# Schematic_withShiftResister.net
KiCad netlist of a schematic drawn in EAGLE
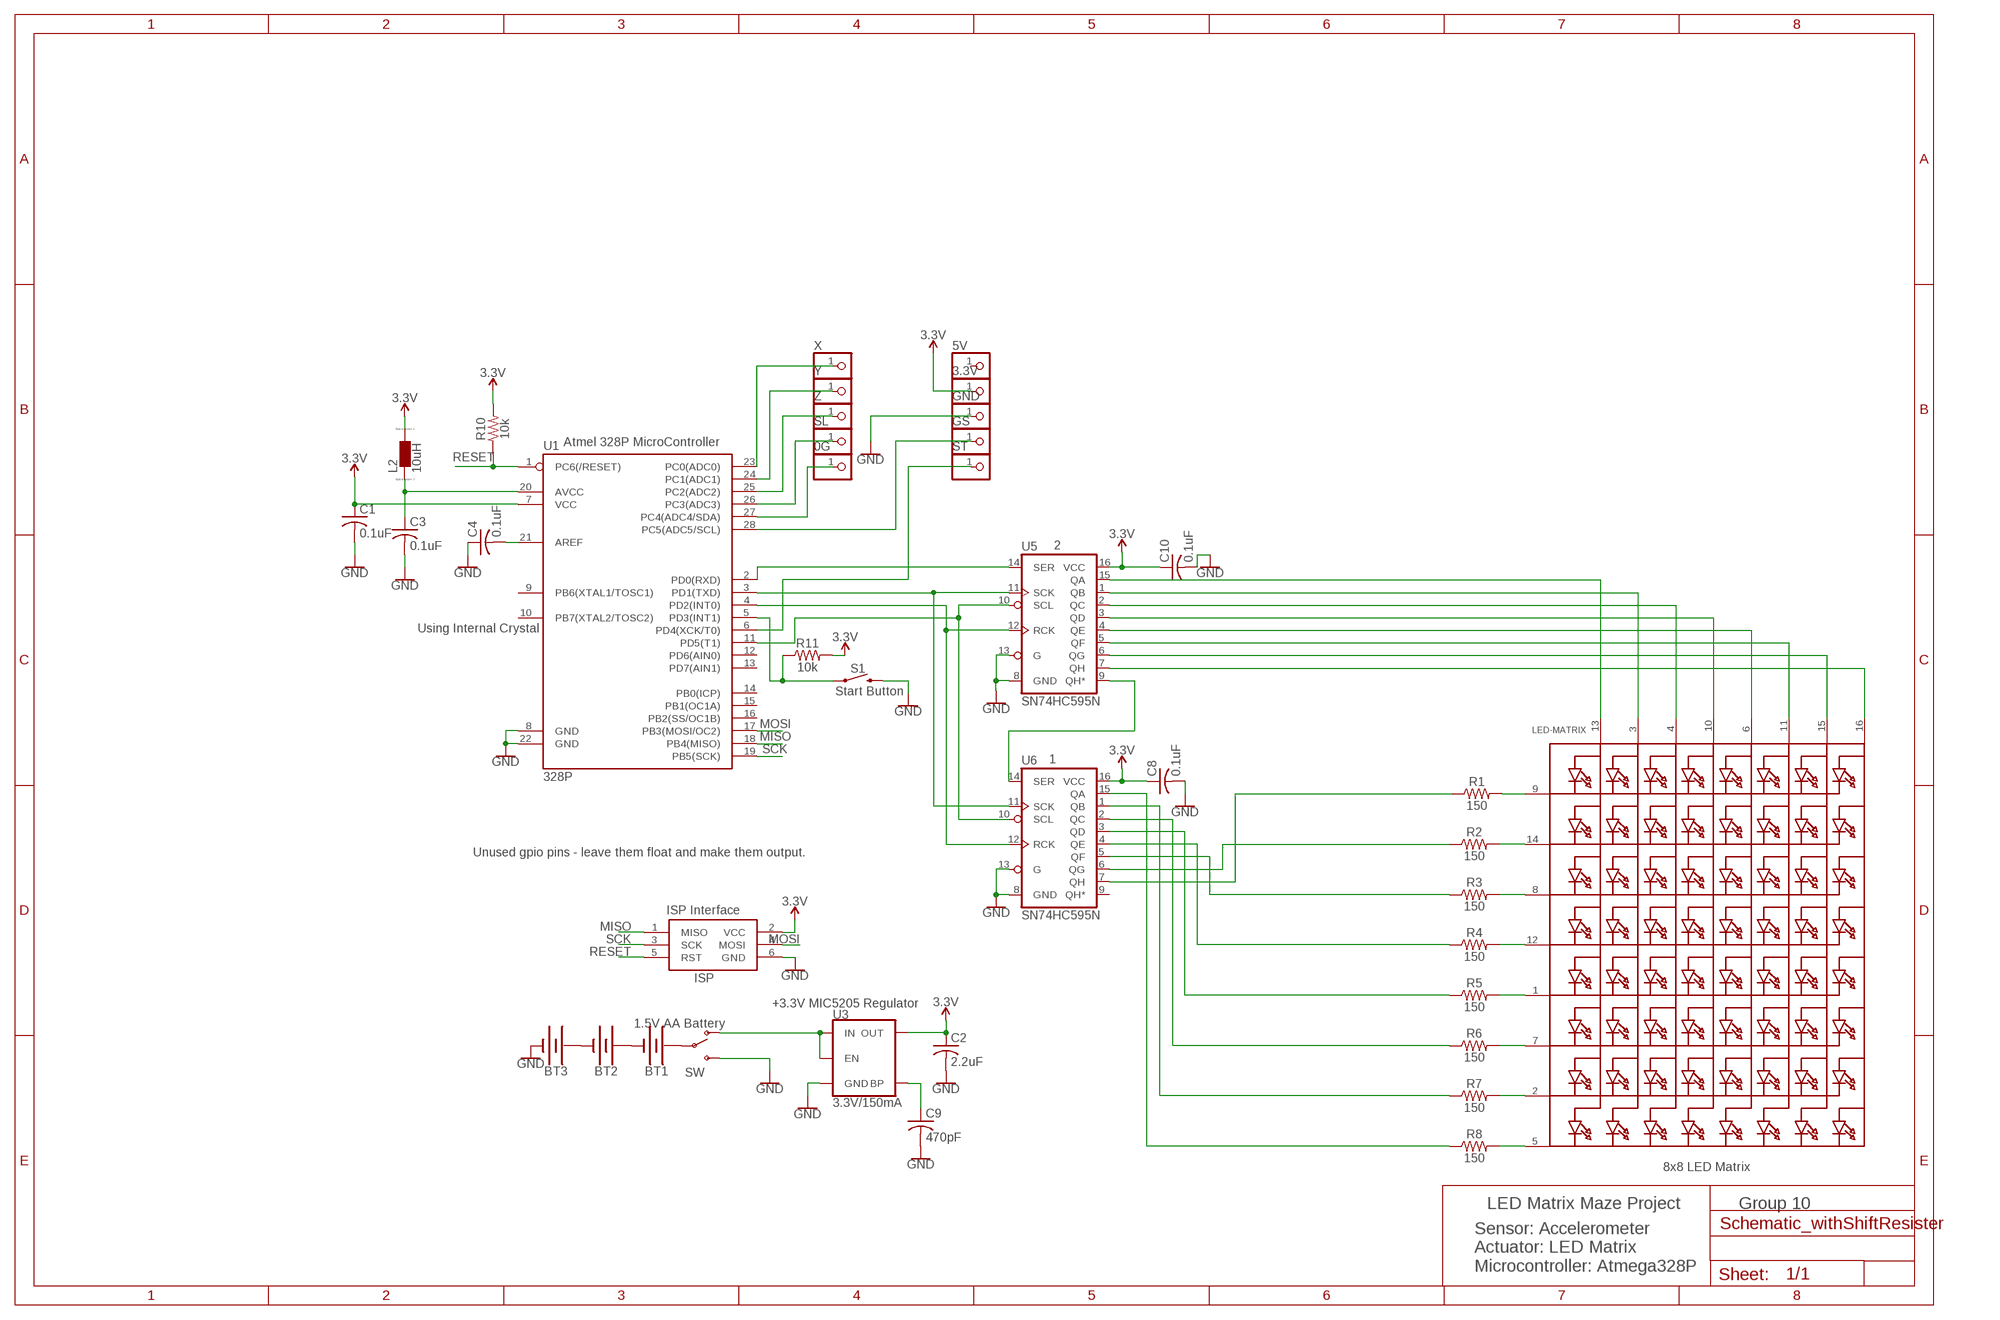
[diagram p0: schematic, sheet 1]

(export (version "E")
  (design (tool "Eeschema 10.0.6"))
  (components
    (comp (ref "0G")
      (value "PINHD-1X1")
      (footprint "eagle-import:1X01")
      (libsource (lib "eagle-import") (part "PINHD-1X1"))
    )
    (comp (ref "3.3V")
      (value "PINHD-1X1")
      (footprint "eagle-import:1X01")
      (libsource (lib "eagle-import") (part "PINHD-1X1"))
    )
    (comp (ref "5V")
      (value "PINHD-1X1")
      (footprint "eagle-import:1X01")
      (libsource (lib "eagle-import") (part "PINHD-1X1"))
    )
    (comp (ref "BT1")
      (value "BATTERY-AAA_KIT")
      (footprint "eagle-import:BATTERY-AAA-KIT")
      (libsource (lib "eagle-import") (part "BATTERY-AAA_KIT"))
    )
    (comp (ref "BT2")
      (value "BATTERY-AAA_KIT")
      (footprint "eagle-import:BATTERY-AAA-KIT")
      (libsource (lib "eagle-import") (part "BATTERY-AAA_KIT"))
    )
    (comp (ref "BT3")
      (value "BATTERY-AAA_KIT")
      (footprint "eagle-import:BATTERY-AAA-KIT")
      (libsource (lib "eagle-import") (part "BATTERY-AAA_KIT"))
    )
    (comp (ref "C1")
      (value "0.1uF")
      (footprint "eagle-import:C0805")
      (libsource (lib "eagle-import") (part "C-USC0805"))
    )
    (comp (ref "C2")
      (value "2.2uF")
      (footprint "eagle-import:C0805")
      (libsource (lib "eagle-import") (part "C-USC0805"))
    )
    (comp (ref "C3")
      (value "0.1uF")
      (footprint "eagle-import:C0805")
      (libsource (lib "eagle-import") (part "C-USC0805"))
    )
    (comp (ref "C4")
      (value "0.1uF")
      (footprint "eagle-import:C0805")
      (libsource (lib "eagle-import") (part "C-USC0805"))
    )
    (comp (ref "C8")
      (value "0.1uF")
      (footprint "eagle-import:C0805")
      (libsource (lib "eagle-import") (part "C-USC0805"))
    )
    (comp (ref "C9")
      (value "470pF")
      (footprint "eagle-import:C0805")
      (libsource (lib "eagle-import") (part "C-USC0805"))
    )
    (comp (ref "C10")
      (value "0.1uF")
      (footprint "eagle-import:C0805")
      (libsource (lib "eagle-import") (part "C-USC0805"))
    )
    (comp (ref "GND")
      (value "PINHD-1X1")
      (footprint "eagle-import:1X01")
      (libsource (lib "eagle-import") (part "PINHD-1X1"))
    )
    (comp (ref "GS")
      (value "PINHD-1X1")
      (footprint "eagle-import:1X01")
      (libsource (lib "eagle-import") (part "PINHD-1X1"))
    )
    (comp (ref "ISP")
      (value "AVRISP-6")
      (footprint "eagle-import:AVRISP")
      (libsource (lib "eagle-import") (part "AVRISP-6"))
    )
    (comp (ref "L2")
      (value "10uH")
      (footprint "eagle-import:L1812")
      (libsource (lib "eagle-import") (part "L"))
    )
    (comp (ref "LED-MATRIX")
      (value "SEGMENT_8X8_ROWCATHODEM12A881UR")
      (footprint "eagle-import:SEGMENT_BL-M12A881UR")
      (libsource (lib "eagle-import") (part "SEGMENT_8X8_ROWCATHODEM12A881UR"))
    )
    (comp (ref "R1")
      (value "150")
      (footprint "eagle-import:0603")
      (libsource (lib "eagle-import") (part "150OHM-0603-1/10W-1%"))
    )
    (comp (ref "R2")
      (value "150")
      (footprint "eagle-import:0603")
      (libsource (lib "eagle-import") (part "150OHM-0603-1/10W-1%"))
    )
    (comp (ref "R3")
      (value "150")
      (footprint "eagle-import:0603")
      (libsource (lib "eagle-import") (part "150OHM-0603-1/10W-1%"))
    )
    (comp (ref "R4")
      (value "150")
      (footprint "eagle-import:0603")
      (libsource (lib "eagle-import") (part "150OHM-0603-1/10W-1%"))
    )
    (comp (ref "R5")
      (value "150")
      (footprint "eagle-import:0603")
      (libsource (lib "eagle-import") (part "150OHM-0603-1/10W-1%"))
    )
    (comp (ref "R6")
      (value "150")
      (footprint "eagle-import:0603")
      (libsource (lib "eagle-import") (part "150OHM-0603-1/10W-1%"))
    )
    (comp (ref "R7")
      (value "150")
      (footprint "eagle-import:0603")
      (libsource (lib "eagle-import") (part "150OHM-0603-1/10W-1%"))
    )
    (comp (ref "R8")
      (value "150")
      (footprint "eagle-import:0603")
      (libsource (lib "eagle-import") (part "150OHM-0603-1/10W-1%"))
    )
    (comp (ref "R10")
      (value "10k")
      (footprint "eagle-import:0603")
      (libsource (lib "eagle-import") (part "10KOHM-0603-1/10W-1%"))
    )
    (comp (ref "R11")
      (value "10k")
      (footprint "eagle-import:0603")
      (libsource (lib "eagle-import") (part "10KOHM-0603-1/10W-1%"))
    )
    (comp (ref "S1")
      (value "MOMENTARY-SWITCH-SPST-PTH-6.0MM")
      (footprint "eagle-import:TACTILE_SWITCH_PTH_6.0MM")
      (libsource (lib "eagle-import") (part "MOMENTARY-SWITCH-SPST-PTH-6.0MM"))
    )
    (comp (ref "SL")
      (value "PINHD-1X1")
      (footprint "eagle-import:1X01")
      (libsource (lib "eagle-import") (part "PINHD-1X1"))
    )
    (comp (ref "ST")
      (value "PINHD-1X1")
      (footprint "eagle-import:1X01")
      (libsource (lib "eagle-import") (part "PINHD-1X1"))
    )
    (comp (ref "SW")
      (value "SWITCH-SPSTPTH_LOCK")
      (footprint "eagle-import:SWITCH-SPDT_LOCK.007S")
      (libsource (lib "eagle-import") (part "SWITCH-SPSTPTH_LOCK"))
    )
    (comp (ref "U1")
      (value "328P")
      (footprint "eagle-import:DIP28")
      (libsource (lib "eagle-import") (part "ATMEGA328P_PDIP"))
    )
    (comp (ref "U3")
      (value "3.3V/150mA")
      (footprint "eagle-import:SOT23-5")
      (libsource (lib "eagle-import") (part "V_REG_MIC52053.3V"))
    )
    (comp (ref "U5")
      (value "SN74HC595N")
      (footprint "eagle-import:DIP16")
      (libsource (lib "eagle-import") (part "74595NHC"))
    )
    (comp (ref "U6")
      (value "SN74HC595N")
      (footprint "eagle-import:DIP16")
      (libsource (lib "eagle-import") (part "74595NHC"))
    )
    (comp (ref "X")
      (value "PINHD-1X1")
      (footprint "eagle-import:1X01")
      (libsource (lib "eagle-import") (part "PINHD-1X1"))
    )
    (comp (ref "Y")
      (value "PINHD-1X1")
      (footprint "eagle-import:1X01")
      (libsource (lib "eagle-import") (part "PINHD-1X1"))
    )
    (comp (ref "Z")
      (value "PINHD-1X1")
      (footprint "eagle-import:1X01")
      (libsource (lib "eagle-import") (part "PINHD-1X1"))
    )
  )
  (nets
    (net (code "1") (name "/MISO") (class "Default")
      (node (ref "ISP") (pin "1") (pinfunction "MISO_1") (pintype "input"))
      (node (ref "U1") (pin "18") (pinfunction "PB4(MISO)_18") (pintype "bidirectional"))
    )
    (net (code "2") (name "/MOSI") (class "Default")
      (node (ref "ISP") (pin "4") (pinfunction "MOSI_4") (pintype "output"))
      (node (ref "U1") (pin "17") (pinfunction "PB3(MOSI/OC2)_17") (pintype "bidirectional"))
    )
    (net (code "3") (name "/RESET") (class "Default")
      (node (ref "ISP") (pin "5") (pinfunction "RST_5") (pintype "output"))
      (node (ref "R10") (pin "1") (pinfunction "1_1") (pintype "passive"))
      (node (ref "U1") (pin "1") (pinfunction "PC6(/RESET)_1") (pintype "bidirectional"))
    )
    (net (code "4") (name "/SCK") (class "Default")
      (node (ref "ISP") (pin "3") (pinfunction "SCK_3") (pintype "output"))
      (node (ref "U1") (pin "19") (pinfunction "PB5(SCK)_19") (pintype "bidirectional"))
    )
    (net (code "5") (name "3.3V") (class "Default")
      (node (ref "3.3V") (pin "1") (pinfunction "1_1") (pintype "passive"))
      (node (ref "C1") (pin "1") (pinfunction "1_1") (pintype "passive"))
      (node (ref "C10") (pin "1") (pinfunction "1_1") (pintype "passive"))
      (node (ref "C2") (pin "1") (pinfunction "1_1") (pintype "passive"))
      (node (ref "C8") (pin "1") (pinfunction "1_1") (pintype "passive"))
      (node (ref "ISP") (pin "2") (pinfunction "VCC_2") (pintype "power_in"))
      (node (ref "L2") (pin "1") (pinfunction "1_1") (pintype "passive"))
      (node (ref "R10") (pin "2") (pinfunction "2_2") (pintype "passive"))
      (node (ref "R11") (pin "2") (pinfunction "2_2") (pintype "passive"))
      (node (ref "U1") (pin "7") (pinfunction "VCC_7") (pintype "bidirectional"))
      (node (ref "U3") (pin "5") (pinfunction "OUT_5") (pintype "passive"))
      (node (ref "U5") (pin "16") (pinfunction "VCC_16") (pintype "power_in"))
      (node (ref "U6") (pin "16") (pinfunction "VCC_16") (pintype "power_in"))
    )
    (net (code "6") (name "GND") (class "Default")
      (node (ref "BT3") (pin "GND@1") (pinfunction "-_GND@1") (pintype "power_in"))
      (node (ref "C1") (pin "2") (pinfunction "2_2") (pintype "passive"))
      (node (ref "C10") (pin "2") (pinfunction "2_2") (pintype "passive"))
      (node (ref "C2") (pin "2") (pinfunction "2_2") (pintype "passive"))
      (node (ref "C3") (pin "2") (pinfunction "2_2") (pintype "passive"))
      (node (ref "C4") (pin "1") (pinfunction "1_1") (pintype "passive"))
      (node (ref "C8") (pin "2") (pinfunction "2_2") (pintype "passive"))
      (node (ref "C9") (pin "2") (pinfunction "2_2") (pintype "passive"))
      (node (ref "GND") (pin "1") (pinfunction "1_1") (pintype "passive"))
      (node (ref "ISP") (pin "6") (pinfunction "GND_6") (pintype "power_in"))
      (node (ref "S1") (pin "3") (pinfunction "2_3") (pintype "passive"))
      (node (ref "SW") (pin "3") (pinfunction "S_3") (pintype "passive"))
      (node (ref "U1") (pin "22") (pinfunction "GND_22") (pintype "bidirectional"))
      (node (ref "U1") (pin "8") (pinfunction "GND_8") (pintype "bidirectional"))
      (node (ref "U3") (pin "2") (pinfunction "GND_2") (pintype "input"))
      (node (ref "U5") (pin "13") (pinfunction "G_13") (pintype "input"))
      (node (ref "U5") (pin "8") (pinfunction "GND_8") (pintype "power_in"))
      (node (ref "U6") (pin "13") (pinfunction "G_13") (pintype "input"))
      (node (ref "U6") (pin "8") (pinfunction "GND_8") (pintype "power_in"))
    )
    (net (code "7") (name "Net-(BT1-+)") (class "Default")
      (node (ref "BT1") (pin "PWR@1") (pinfunction "+_PWR@1") (pintype "power_in"))
      (node (ref "SW") (pin "2") (pinfunction "P_2") (pintype "passive"))
    )
    (net (code "8") (name "Net-(BT1--)") (class "Default")
      (node (ref "BT1") (pin "GND@1") (pinfunction "-_GND@1") (pintype "power_in"))
      (node (ref "BT2") (pin "PWR@1") (pinfunction "+_PWR@1") (pintype "power_in"))
    )
    (net (code "9") (name "Net-(BT2--)") (class "Default")
      (node (ref "BT2") (pin "GND@1") (pinfunction "-_GND@1") (pintype "power_in"))
      (node (ref "BT3") (pin "PWR@1") (pinfunction "+_PWR@1") (pintype "power_in"))
    )
    (net (code "10") (name "Net-(LED-MATRIX-A1)") (class "Default")
      (node (ref "LED-MATRIX") (pin "13") (pinfunction "A1_13") (pintype "bidirectional"))
      (node (ref "U5") (pin "15") (pinfunction "QA_15") (pintype "tri_state"))
    )
    (net (code "11") (name "Net-(LED-MATRIX-A2)") (class "Default")
      (node (ref "LED-MATRIX") (pin "3") (pinfunction "A2_3") (pintype "bidirectional"))
      (node (ref "U5") (pin "1") (pinfunction "QB_1") (pintype "tri_state"))
    )
    (net (code "12") (name "Net-(LED-MATRIX-A3)") (class "Default")
      (node (ref "LED-MATRIX") (pin "4") (pinfunction "A3_4") (pintype "bidirectional"))
      (node (ref "U5") (pin "2") (pinfunction "QC_2") (pintype "tri_state"))
    )
    (net (code "13") (name "Net-(LED-MATRIX-A4)") (class "Default")
      (node (ref "LED-MATRIX") (pin "10") (pinfunction "A4_10") (pintype "bidirectional"))
      (node (ref "U5") (pin "3") (pinfunction "QD_3") (pintype "tri_state"))
    )
    (net (code "14") (name "Net-(LED-MATRIX-A5)") (class "Default")
      (node (ref "LED-MATRIX") (pin "6") (pinfunction "A5_6") (pintype "bidirectional"))
      (node (ref "U5") (pin "4") (pinfunction "QE_4") (pintype "tri_state"))
    )
    (net (code "15") (name "Net-(LED-MATRIX-A6)") (class "Default")
      (node (ref "LED-MATRIX") (pin "11") (pinfunction "A6_11") (pintype "bidirectional"))
      (node (ref "U5") (pin "5") (pinfunction "QF_5") (pintype "tri_state"))
    )
    (net (code "16") (name "Net-(LED-MATRIX-A7)") (class "Default")
      (node (ref "LED-MATRIX") (pin "15") (pinfunction "A7_15") (pintype "bidirectional"))
      (node (ref "U5") (pin "6") (pinfunction "QG_6") (pintype "tri_state"))
    )
    (net (code "17") (name "Net-(LED-MATRIX-A8)") (class "Default")
      (node (ref "LED-MATRIX") (pin "16") (pinfunction "A8_16") (pintype "bidirectional"))
      (node (ref "U5") (pin "7") (pinfunction "QH_7") (pintype "tri_state"))
    )
    (net (code "18") (name "Net-(LED-MATRIX-K1)") (class "Default")
      (node (ref "LED-MATRIX") (pin "9") (pinfunction "K1_9") (pintype "bidirectional"))
      (node (ref "R1") (pin "2") (pinfunction "2_2") (pintype "passive"))
    )
    (net (code "19") (name "Net-(LED-MATRIX-K2)") (class "Default")
      (node (ref "LED-MATRIX") (pin "14") (pinfunction "K2_14") (pintype "bidirectional"))
      (node (ref "R2") (pin "2") (pinfunction "2_2") (pintype "passive"))
    )
    (net (code "20") (name "Net-(LED-MATRIX-K3)") (class "Default")
      (node (ref "LED-MATRIX") (pin "8") (pinfunction "K3_8") (pintype "bidirectional"))
      (node (ref "R3") (pin "2") (pinfunction "2_2") (pintype "passive"))
    )
    (net (code "21") (name "Net-(LED-MATRIX-K4)") (class "Default")
      (node (ref "LED-MATRIX") (pin "12") (pinfunction "K4_12") (pintype "bidirectional"))
      (node (ref "R4") (pin "2") (pinfunction "2_2") (pintype "passive"))
    )
    (net (code "22") (name "Net-(LED-MATRIX-K5)") (class "Default")
      (node (ref "LED-MATRIX") (pin "1") (pinfunction "K5_1") (pintype "bidirectional"))
      (node (ref "R5") (pin "2") (pinfunction "2_2") (pintype "passive"))
    )
    (net (code "23") (name "Net-(LED-MATRIX-K6)") (class "Default")
      (node (ref "LED-MATRIX") (pin "7") (pinfunction "K6_7") (pintype "bidirectional"))
      (node (ref "R6") (pin "2") (pinfunction "2_2") (pintype "passive"))
    )
    (net (code "24") (name "Net-(LED-MATRIX-K7)") (class "Default")
      (node (ref "LED-MATRIX") (pin "2") (pinfunction "K7_2") (pintype "bidirectional"))
      (node (ref "R7") (pin "2") (pinfunction "2_2") (pintype "passive"))
    )
    (net (code "25") (name "Net-(LED-MATRIX-K8)") (class "Default")
      (node (ref "LED-MATRIX") (pin "5") (pinfunction "K8_5") (pintype "bidirectional"))
      (node (ref "R8") (pin "2") (pinfunction "2_2") (pintype "passive"))
    )
    (net (code "26") (name "Net-(SW-O)") (class "Default")
      (node (ref "SW") (pin "1") (pinfunction "O_1") (pintype "passive"))
      (node (ref "U3") (pin "1") (pinfunction "IN_1") (pintype "input"))
      (node (ref "U3") (pin "3") (pinfunction "EN_3") (pintype "input"))
    )
    (net (code "27") (name "Net-(U1-AREF)") (class "Default")
      (node (ref "C4") (pin "2") (pinfunction "2_2") (pintype "passive"))
      (node (ref "U1") (pin "21") (pinfunction "AREF_21") (pintype "bidirectional"))
    )
    (net (code "28") (name "Net-(U1-AVCC)") (class "Default")
      (node (ref "C3") (pin "1") (pinfunction "1_1") (pintype "passive"))
      (node (ref "L2") (pin "2") (pinfunction "2_2") (pintype "passive"))
      (node (ref "U1") (pin "20") (pinfunction "AVCC_20") (pintype "bidirectional"))
    )
    (net (code "29") (name "Net-(U1-PC0(ADC0))") (class "Default")
      (node (ref "U1") (pin "23") (pinfunction "PC0(ADC0)_23") (pintype "bidirectional"))
      (node (ref "X") (pin "1") (pinfunction "1_1") (pintype "passive"))
    )
    (net (code "30") (name "Net-(U1-PC1(ADC1))") (class "Default")
      (node (ref "U1") (pin "24") (pinfunction "PC1(ADC1)_24") (pintype "bidirectional"))
      (node (ref "Y") (pin "1") (pinfunction "1_1") (pintype "passive"))
    )
    (net (code "31") (name "Net-(U1-PC2(ADC2))") (class "Default")
      (node (ref "U1") (pin "25") (pinfunction "PC2(ADC2)_25") (pintype "bidirectional"))
      (node (ref "Z") (pin "1") (pinfunction "1_1") (pintype "passive"))
    )
    (net (code "32") (name "Net-(U1-PC3(ADC3))") (class "Default")
      (node (ref "SL") (pin "1") (pinfunction "1_1") (pintype "passive"))
      (node (ref "U1") (pin "26") (pinfunction "PC3(ADC3)_26") (pintype "bidirectional"))
    )
    (net (code "33") (name "Net-(U1-PC4(ADC4{slash}SDA))") (class "Default")
      (node (ref "0G") (pin "1") (pinfunction "1_1") (pintype "passive"))
      (node (ref "U1") (pin "27") (pinfunction "PC4(ADC4/SDA)_27") (pintype "bidirectional"))
    )
    (net (code "34") (name "Net-(U1-PC5(ADC5{slash}SCL))") (class "Default")
      (node (ref "GS") (pin "1") (pinfunction "1_1") (pintype "passive"))
      (node (ref "U1") (pin "28") (pinfunction "PC5(ADC5/SCL)_28") (pintype "bidirectional"))
    )
    (net (code "35") (name "Net-(U1-PD0(RXD))") (class "Default")
      (node (ref "U1") (pin "2") (pinfunction "PD0(RXD)_2") (pintype "bidirectional"))
      (node (ref "U5") (pin "14") (pinfunction "SER_14") (pintype "input"))
    )
    (net (code "36") (name "Net-(U1-PD1(TXD))") (class "Default")
      (node (ref "U1") (pin "3") (pinfunction "PD1(TXD)_3") (pintype "bidirectional"))
      (node (ref "U5") (pin "11") (pinfunction "SCK_11") (pintype "input"))
      (node (ref "U6") (pin "11") (pinfunction "SCK_11") (pintype "input"))
    )
    (net (code "37") (name "Net-(U1-PD2(INT0))") (class "Default")
      (node (ref "U1") (pin "4") (pinfunction "PD2(INT0)_4") (pintype "bidirectional"))
      (node (ref "U5") (pin "12") (pinfunction "RCK_12") (pintype "input"))
      (node (ref "U6") (pin "12") (pinfunction "RCK_12") (pintype "input"))
    )
    (net (code "38") (name "Net-(U1-PD3(INT1))") (class "Default")
      (node (ref "R11") (pin "1") (pinfunction "1_1") (pintype "passive"))
      (node (ref "S1") (pin "1") (pinfunction "1_1") (pintype "passive"))
      (node (ref "U1") (pin "5") (pinfunction "PD3(INT1)_5") (pintype "bidirectional"))
    )
    (net (code "39") (name "Net-(U1-PD4(XCK{slash}T0))") (class "Default")
      (node (ref "ST") (pin "1") (pinfunction "1_1") (pintype "passive"))
      (node (ref "U1") (pin "6") (pinfunction "PD4(XCK/T0)_6") (pintype "bidirectional"))
    )
    (net (code "40") (name "Net-(U1-PD5(T1))") (class "Default")
      (node (ref "U1") (pin "11") (pinfunction "PD5(T1)_11") (pintype "bidirectional"))
      (node (ref "U5") (pin "10") (pinfunction "SCL_10") (pintype "input"))
      (node (ref "U6") (pin "10") (pinfunction "SCL_10") (pintype "input"))
    )
    (net (code "41") (name "Net-(U3-BP)") (class "Default")
      (node (ref "C9") (pin "1") (pinfunction "1_1") (pintype "passive"))
      (node (ref "U3") (pin "4") (pinfunction "BP_4") (pintype "input"))
    )
    (net (code "42") (name "Net-(U5-QH*)") (class "Default")
      (node (ref "U5") (pin "9") (pinfunction "QH*_9") (pintype "tri_state"))
      (node (ref "U6") (pin "14") (pinfunction "SER_14") (pintype "input"))
    )
    (net (code "43") (name "Net-(U6-QA)") (class "Default")
      (node (ref "R8") (pin "1") (pinfunction "1_1") (pintype "passive"))
      (node (ref "U6") (pin "15") (pinfunction "QA_15") (pintype "tri_state"))
    )
    (net (code "44") (name "Net-(U6-QB)") (class "Default")
      (node (ref "R7") (pin "1") (pinfunction "1_1") (pintype "passive"))
      (node (ref "U6") (pin "1") (pinfunction "QB_1") (pintype "tri_state"))
    )
    (net (code "45") (name "Net-(U6-QC)") (class "Default")
      (node (ref "R6") (pin "1") (pinfunction "1_1") (pintype "passive"))
      (node (ref "U6") (pin "2") (pinfunction "QC_2") (pintype "tri_state"))
    )
    (net (code "46") (name "Net-(U6-QD)") (class "Default")
      (node (ref "R5") (pin "1") (pinfunction "1_1") (pintype "passive"))
      (node (ref "U6") (pin "3") (pinfunction "QD_3") (pintype "tri_state"))
    )
    (net (code "47") (name "Net-(U6-QE)") (class "Default")
      (node (ref "R4") (pin "1") (pinfunction "1_1") (pintype "passive"))
      (node (ref "U6") (pin "4") (pinfunction "QE_4") (pintype "tri_state"))
    )
    (net (code "48") (name "Net-(U6-QF)") (class "Default")
      (node (ref "R3") (pin "1") (pinfunction "1_1") (pintype "passive"))
      (node (ref "U6") (pin "5") (pinfunction "QF_5") (pintype "tri_state"))
    )
    (net (code "49") (name "Net-(U6-QG)") (class "Default")
      (node (ref "R2") (pin "1") (pinfunction "1_1") (pintype "passive"))
      (node (ref "U6") (pin "6") (pinfunction "QG_6") (pintype "tri_state"))
    )
    (net (code "50") (name "Net-(U6-QH)") (class "Default")
      (node (ref "R1") (pin "1") (pinfunction "1_1") (pintype "passive"))
      (node (ref "U6") (pin "7") (pinfunction "QH_7") (pintype "tri_state"))
    )
    (net (code "51") (name "unconnected-(5V-Pad1)") (class "Default")
      (node (ref "5V") (pin "1") (pinfunction "1_1") (pintype "passive"))
    )
    (net (code "52") (name "unconnected-(U1-PB0(ICP)-Pad14)") (class "Default")
      (node (ref "U1") (pin "14") (pinfunction "PB0(ICP)_14") (pintype "bidirectional"))
    )
    (net (code "53") (name "unconnected-(U1-PB1(OC1A)-Pad15)") (class "Default")
      (node (ref "U1") (pin "15") (pinfunction "PB1(OC1A)_15") (pintype "bidirectional"))
    )
    (net (code "54") (name "unconnected-(U1-PB2(SS{slash}OC1B)-Pad16)") (class "Default")
      (node (ref "U1") (pin "16") (pinfunction "PB2(SS/OC1B)_16") (pintype "bidirectional"))
    )
    (net (code "55") (name "unconnected-(U1-PB6(XTAL1{slash}TOSC1)-Pad9)") (class "Default")
      (node (ref "U1") (pin "9") (pinfunction "PB6(XTAL1/TOSC1)_9") (pintype "bidirectional"))
    )
    (net (code "56") (name "unconnected-(U1-PB7(XTAL2{slash}TOSC2)-Pad10)") (class "Default")
      (node (ref "U1") (pin "10") (pinfunction "PB7(XTAL2/TOSC2)_10") (pintype "bidirectional"))
    )
    (net (code "57") (name "unconnected-(U1-PD6(AIN0)-Pad12)") (class "Default")
      (node (ref "U1") (pin "12") (pinfunction "PD6(AIN0)_12") (pintype "bidirectional"))
    )
    (net (code "58") (name "unconnected-(U1-PD7(AIN1)-Pad13)") (class "Default")
      (node (ref "U1") (pin "13") (pinfunction "PD7(AIN1)_13") (pintype "bidirectional"))
    )
    (net (code "59") (name "unconnected-(U6-QH*-Pad9)") (class "Default")
      (node (ref "U6") (pin "9") (pinfunction "QH*_9") (pintype "tri_state"))
    )
  )
)
